# SALS.net
KiCad netlist of a schematic drawn in EAGLE
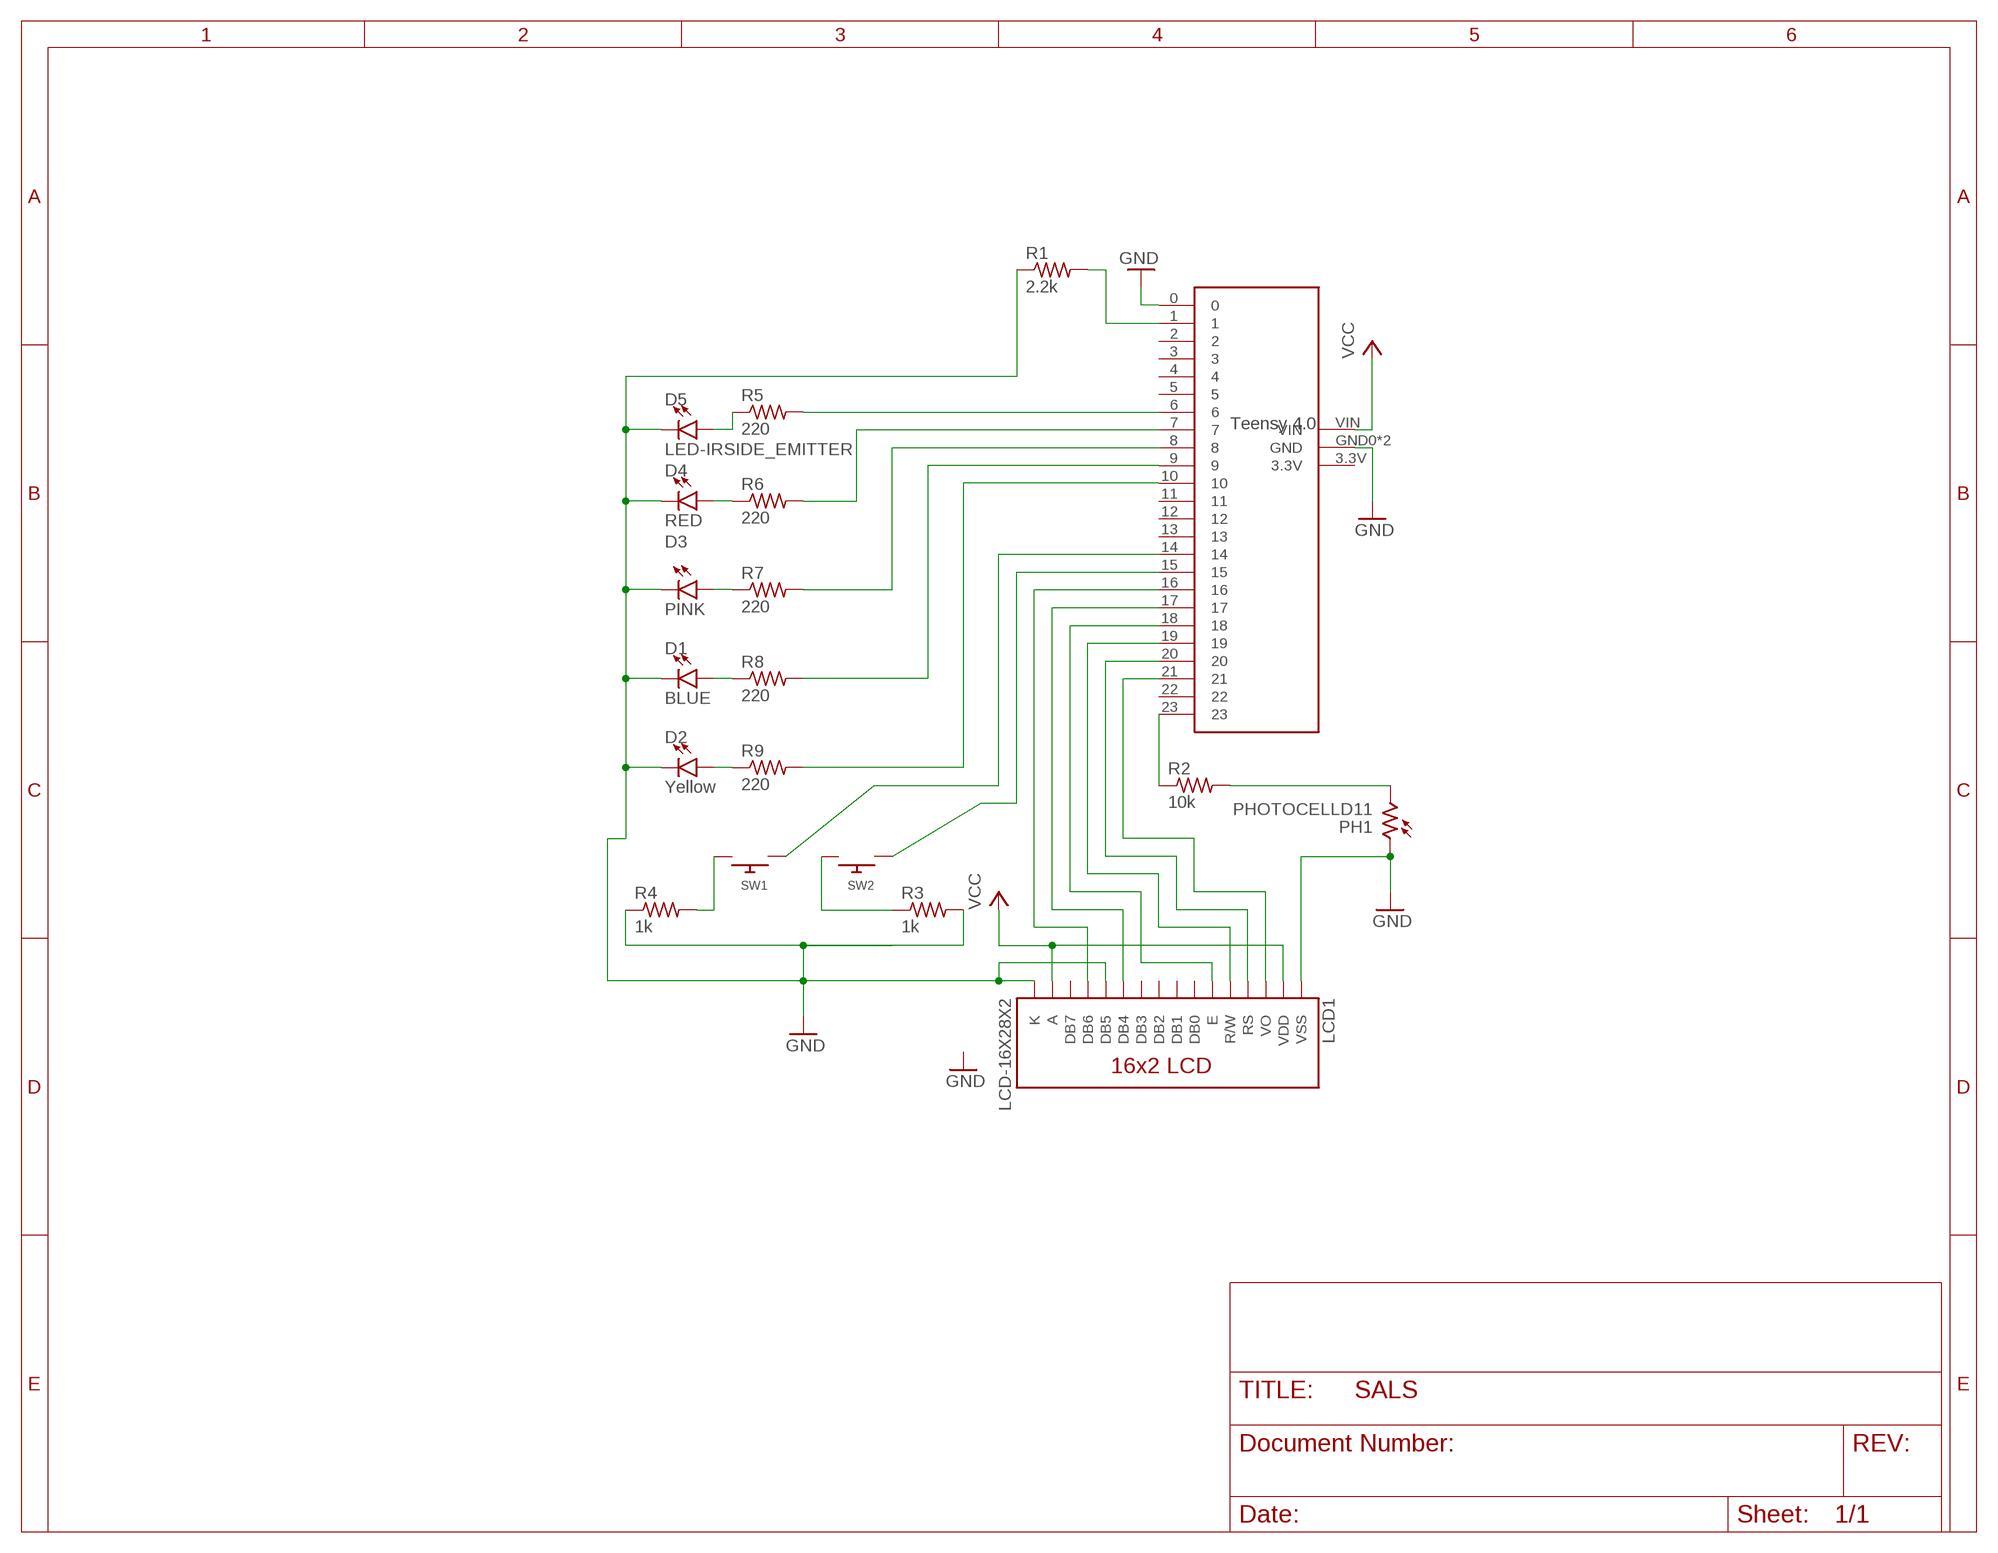
[diagram p0: schematic, sheet 1]

(export (version "E")
  (design (tool "Eeschema 10.0.6"))
  (components
    (comp (ref "D1")
      (value "BLUE")
      (footprint "eagle-import:LED-0603")
      (libsource (lib "eagle-import") (part "LED-BLUE0603"))
    )
    (comp (ref "D2")
      (value "Yellow")
      (footprint "eagle-import:LED-0603")
      (libsource (lib "eagle-import") (part "LED-YELLOW0603"))
    )
    (comp (ref "D3")
      (value "PINK")
      (footprint "eagle-import:LED-1206")
      (libsource (lib "eagle-import") (part "LED-PINK1206"))
    )
    (comp (ref "D4")
      (value "RED")
      (footprint "eagle-import:LED-0603")
      (libsource (lib "eagle-import") (part "LED-RED0603"))
    )
    (comp (ref "D5")
      (value "LED-IRSIDE_EMITTER")
      (footprint "eagle-import:LTE-302")
      (libsource (lib "eagle-import") (part "LED-IRSIDE_EMITTER"))
    )
    (comp (ref "LCD1")
      (value "LCD-16X28X2")
      (footprint "eagle-import:LCD-8X2")
      (libsource (lib "eagle-import") (part "LCD-16X28X2"))
    )
    (comp (ref "PH1")
      (value "PHOTOCELLD11")
      (footprint "eagle-import:D11XX_H")
      (libsource (lib "eagle-import") (part "PHOTOCELLD11"))
    )
    (comp (ref "R1")
      (value "2.2k")
      (footprint "eagle-import:0204_5")
      (libsource (lib "eagle-import") (part "R-US_0204/5"))
    )
    (comp (ref "R2")
      (value "10k")
      (footprint "eagle-import:0204_5")
      (libsource (lib "eagle-import") (part "R-US_0204/5"))
    )
    (comp (ref "R3")
      (value "1k")
      (footprint "eagle-import:0204_5")
      (libsource (lib "eagle-import") (part "R-US_0204/5"))
    )
    (comp (ref "R4")
      (value "1k")
      (footprint "eagle-import:0204_5")
      (libsource (lib "eagle-import") (part "R-US_0204/5"))
    )
    (comp (ref "R5")
      (value "220")
      (footprint "eagle-import:0204_5")
      (libsource (lib "eagle-import") (part "R-US_0204/5"))
    )
    (comp (ref "R6")
      (value "220")
      (footprint "eagle-import:0204_5")
      (libsource (lib "eagle-import") (part "R-US_0204/5"))
    )
    (comp (ref "R7")
      (value "220")
      (footprint "eagle-import:0204_5")
      (libsource (lib "eagle-import") (part "R-US_0204/5"))
    )
    (comp (ref "R8")
      (value "220")
      (footprint "eagle-import:0204_5")
      (libsource (lib "eagle-import") (part "R-US_0204/5"))
    )
    (comp (ref "R9")
      (value "220")
      (footprint "eagle-import:0204_5")
      (libsource (lib "eagle-import") (part "R-US_0204/5"))
    )
    (comp (ref "SW1")
      (value "SWITCH_PUSHBUTTONEVQ-PE")
      (footprint "eagle-import:TACT_PANA-EVQ")
      (libsource (lib "eagle-import") (part "SWITCH_PUSHBUTTONEVQ-PE"))
    )
    (comp (ref "SW2")
      (value "SWITCH_PUSHBUTTONEVQ-PE")
      (footprint "eagle-import:TACT_PANA-EVQ")
      (libsource (lib "eagle-import") (part "SWITCH_PUSHBUTTONEVQ-PE"))
    )
    (comp (ref "U$1")
      (value "TEENSY_4.0")
      (footprint "eagle-import:TEENSY_4.0")
      (fields (field (name "TYPE") "Teensy 4.0"))
      (libsource (lib "eagle-import") (part "TEENSY_4.0"))
    )
  )
  (nets
    (net (code "1") (name "GND") (class "Default")
      (node (ref "D1") (pin "C") (pinfunction "C_C") (pintype "passive"))
      (node (ref "D2") (pin "C") (pinfunction "C_C") (pintype "passive"))
      (node (ref "D3") (pin "C") (pinfunction "C_C") (pintype "passive"))
      (node (ref "D4") (pin "C") (pinfunction "C_C") (pintype "passive"))
      (node (ref "D5") (pin "C") (pinfunction "C_C") (pintype "passive"))
      (node (ref "LCD1") (pin "1") (pinfunction "VSS_1") (pintype "power_in"))
      (node (ref "LCD1") (pin "12") (pinfunction "DB5_12") (pintype "bidirectional"))
      (node (ref "LCD1") (pin "16") (pinfunction "K_16") (pintype "power_in"))
      (node (ref "PH1") (pin "1") (pinfunction "1_1") (pintype "passive"))
      (node (ref "R1") (pin "1") (pinfunction "1_1") (pintype "passive"))
      (node (ref "R3") (pin "2") (pinfunction "2_2") (pintype "passive"))
      (node (ref "R4") (pin "1") (pinfunction "1_1") (pintype "passive"))
      (node (ref "U$1") (pin "0") (pinfunction "0_0") (pintype "bidirectional"))
      (node (ref "U$1") (pin "GND0") (pinfunction "GND_GND0") (pintype "bidirectional"))
      (node (ref "U$1") (pin "GND1") (pinfunction "GND_GND1") (pintype "bidirectional"))
    )
    (net (code "2") (name "Net-(D1-PadA)") (class "Default")
      (node (ref "D1") (pin "A") (pinfunction "A_A") (pintype "passive"))
      (node (ref "R8") (pin "1") (pinfunction "1_1") (pintype "passive"))
    )
    (net (code "3") (name "Net-(D2-PadA)") (class "Default")
      (node (ref "D2") (pin "A") (pinfunction "A_A") (pintype "passive"))
      (node (ref "R9") (pin "1") (pinfunction "1_1") (pintype "passive"))
    )
    (net (code "4") (name "Net-(D3-PadA)") (class "Default")
      (node (ref "D3") (pin "A") (pinfunction "A_A") (pintype "passive"))
      (node (ref "R7") (pin "1") (pinfunction "1_1") (pintype "passive"))
    )
    (net (code "5") (name "Net-(D4-PadA)") (class "Default")
      (node (ref "D4") (pin "A") (pinfunction "A_A") (pintype "passive"))
      (node (ref "R6") (pin "1") (pinfunction "1_1") (pintype "passive"))
    )
    (net (code "6") (name "Net-(D5-PadA)") (class "Default")
      (node (ref "D5") (pin "A") (pinfunction "A_A") (pintype "passive"))
      (node (ref "R5") (pin "1") (pinfunction "1_1") (pintype "passive"))
    )
    (net (code "7") (name "Net-(LCD1-DB4)") (class "Default")
      (node (ref "LCD1") (pin "11") (pinfunction "DB4_11") (pintype "bidirectional"))
      (node (ref "U$1") (pin "17") (pinfunction "17_17") (pintype "bidirectional"))
    )
    (net (code "8") (name "Net-(LCD1-DB6)") (class "Default")
      (node (ref "LCD1") (pin "13") (pinfunction "DB6_13") (pintype "bidirectional"))
      (node (ref "U$1") (pin "16") (pinfunction "16_16") (pintype "bidirectional"))
    )
    (net (code "9") (name "Net-(LCD1-E)") (class "Default")
      (node (ref "LCD1") (pin "6") (pinfunction "E_6") (pintype "input"))
      (node (ref "U$1") (pin "18") (pinfunction "18_18") (pintype "bidirectional"))
    )
    (net (code "10") (name "Net-(LCD1-RS)") (class "Default")
      (node (ref "LCD1") (pin "4") (pinfunction "RS_4") (pintype "input"))
      (node (ref "U$1") (pin "20") (pinfunction "20_20") (pintype "bidirectional"))
    )
    (net (code "11") (name "Net-(LCD1-R{slash}W)") (class "Default")
      (node (ref "LCD1") (pin "5") (pinfunction "R/W_5") (pintype "input"))
      (node (ref "U$1") (pin "19") (pinfunction "19_19") (pintype "bidirectional"))
    )
    (net (code "12") (name "Net-(LCD1-VO)") (class "Default")
      (node (ref "LCD1") (pin "3") (pinfunction "VO_3") (pintype "bidirectional"))
      (node (ref "U$1") (pin "21") (pinfunction "21_21") (pintype "bidirectional"))
    )
    (net (code "13") (name "Net-(PH1-Pad2)") (class "Default")
      (node (ref "PH1") (pin "2") (pinfunction "2_2") (pintype "passive"))
      (node (ref "R2") (pin "2") (pinfunction "2_2") (pintype "passive"))
    )
    (net (code "14") (name "Net-(R1-Pad2)") (class "Default")
      (node (ref "R1") (pin "2") (pinfunction "2_2") (pintype "passive"))
      (node (ref "U$1") (pin "1") (pinfunction "1_1") (pintype "bidirectional"))
    )
    (net (code "15") (name "Net-(R2-Pad1)") (class "Default")
      (node (ref "R2") (pin "1") (pinfunction "1_1") (pintype "passive"))
      (node (ref "U$1") (pin "23") (pinfunction "23_23") (pintype "bidirectional"))
    )
    (net (code "16") (name "Net-(R3-Pad1)") (class "Default")
      (node (ref "R3") (pin "1") (pinfunction "1_1") (pintype "passive"))
      (node (ref "SW2") (pin "P$2") (pinfunction "P$2_P$2") (pintype "passive"))
    )
    (net (code "17") (name "Net-(R4-Pad2)") (class "Default")
      (node (ref "R4") (pin "2") (pinfunction "2_2") (pintype "passive"))
      (node (ref "SW1") (pin "P$2") (pinfunction "P$2_P$2") (pintype "passive"))
    )
    (net (code "18") (name "Net-(R5-Pad2)") (class "Default")
      (node (ref "R5") (pin "2") (pinfunction "2_2") (pintype "passive"))
      (node (ref "U$1") (pin "6") (pinfunction "6_6") (pintype "bidirectional"))
    )
    (net (code "19") (name "Net-(R6-Pad2)") (class "Default")
      (node (ref "R6") (pin "2") (pinfunction "2_2") (pintype "passive"))
      (node (ref "U$1") (pin "7") (pinfunction "7_7") (pintype "bidirectional"))
    )
    (net (code "20") (name "Net-(R7-Pad2)") (class "Default")
      (node (ref "R7") (pin "2") (pinfunction "2_2") (pintype "passive"))
      (node (ref "U$1") (pin "8") (pinfunction "8_8") (pintype "bidirectional"))
    )
    (net (code "21") (name "Net-(R8-Pad2)") (class "Default")
      (node (ref "R8") (pin "2") (pinfunction "2_2") (pintype "passive"))
      (node (ref "U$1") (pin "9") (pinfunction "9_9") (pintype "bidirectional"))
    )
    (net (code "22") (name "Net-(R9-Pad2)") (class "Default")
      (node (ref "R9") (pin "2") (pinfunction "2_2") (pintype "passive"))
      (node (ref "U$1") (pin "10") (pinfunction "10_10") (pintype "bidirectional"))
    )
    (net (code "23") (name "Net-(SW1-PadP$1)") (class "Default")
      (node (ref "SW1") (pin "P$1") (pinfunction "P$1_P$1") (pintype "passive"))
      (node (ref "U$1") (pin "14") (pinfunction "14_14") (pintype "bidirectional"))
    )
    (net (code "24") (name "Net-(SW2-PadP$1)") (class "Default")
      (node (ref "SW2") (pin "P$1") (pinfunction "P$1_P$1") (pintype "passive"))
      (node (ref "U$1") (pin "15") (pinfunction "15_15") (pintype "bidirectional"))
    )
    (net (code "25") (name "VCC") (class "Default")
      (node (ref "LCD1") (pin "15") (pinfunction "A_15") (pintype "power_in"))
      (node (ref "LCD1") (pin "2") (pinfunction "VDD_2") (pintype "power_in"))
      (node (ref "U$1") (pin "VIN") (pinfunction "VIN_VIN") (pintype "bidirectional"))
    )
    (net (code "26") (name "unconnected-(LCD1-DB0-Pad7)") (class "Default")
      (node (ref "LCD1") (pin "7") (pinfunction "DB0_7") (pintype "bidirectional"))
    )
    (net (code "27") (name "unconnected-(LCD1-DB1-Pad8)") (class "Default")
      (node (ref "LCD1") (pin "8") (pinfunction "DB1_8") (pintype "bidirectional"))
    )
    (net (code "28") (name "unconnected-(LCD1-DB2-Pad9)") (class "Default")
      (node (ref "LCD1") (pin "9") (pinfunction "DB2_9") (pintype "bidirectional"))
    )
    (net (code "29") (name "unconnected-(LCD1-DB3-Pad10)") (class "Default")
      (node (ref "LCD1") (pin "10") (pinfunction "DB3_10") (pintype "bidirectional"))
    )
    (net (code "30") (name "unconnected-(LCD1-DB7-Pad14)") (class "Default")
      (node (ref "LCD1") (pin "14") (pinfunction "DB7_14") (pintype "bidirectional"))
    )
    (net (code "31") (name "unconnected-(U$1-Pad2)") (class "Default")
      (node (ref "U$1") (pin "2") (pinfunction "2_2") (pintype "bidirectional"))
    )
    (net (code "32") (name "unconnected-(U$1-Pad3)") (class "Default")
      (node (ref "U$1") (pin "3") (pinfunction "3_3") (pintype "bidirectional"))
    )
    (net (code "33") (name "unconnected-(U$1-Pad3.3V)") (class "Default")
      (node (ref "U$1") (pin "3.3V") (pinfunction "3.3V_3.3V") (pintype "bidirectional"))
    )
    (net (code "34") (name "unconnected-(U$1-Pad4)") (class "Default")
      (node (ref "U$1") (pin "4") (pinfunction "4_4") (pintype "bidirectional"))
    )
    (net (code "35") (name "unconnected-(U$1-Pad5)") (class "Default")
      (node (ref "U$1") (pin "5") (pinfunction "5_5") (pintype "bidirectional"))
    )
    (net (code "36") (name "unconnected-(U$1-Pad11)") (class "Default")
      (node (ref "U$1") (pin "11") (pinfunction "11_11") (pintype "bidirectional"))
    )
    (net (code "37") (name "unconnected-(U$1-Pad12)") (class "Default")
      (node (ref "U$1") (pin "12") (pinfunction "12_12") (pintype "bidirectional"))
    )
    (net (code "38") (name "unconnected-(U$1-Pad13)") (class "Default")
      (node (ref "U$1") (pin "13") (pinfunction "13_13") (pintype "bidirectional"))
    )
    (net (code "39") (name "unconnected-(U$1-Pad22)") (class "Default")
      (node (ref "U$1") (pin "22") (pinfunction "22_22") (pintype "bidirectional"))
    )
  )
)
